# basic.net
KiCad netlist of a schematic drawn in EAGLE
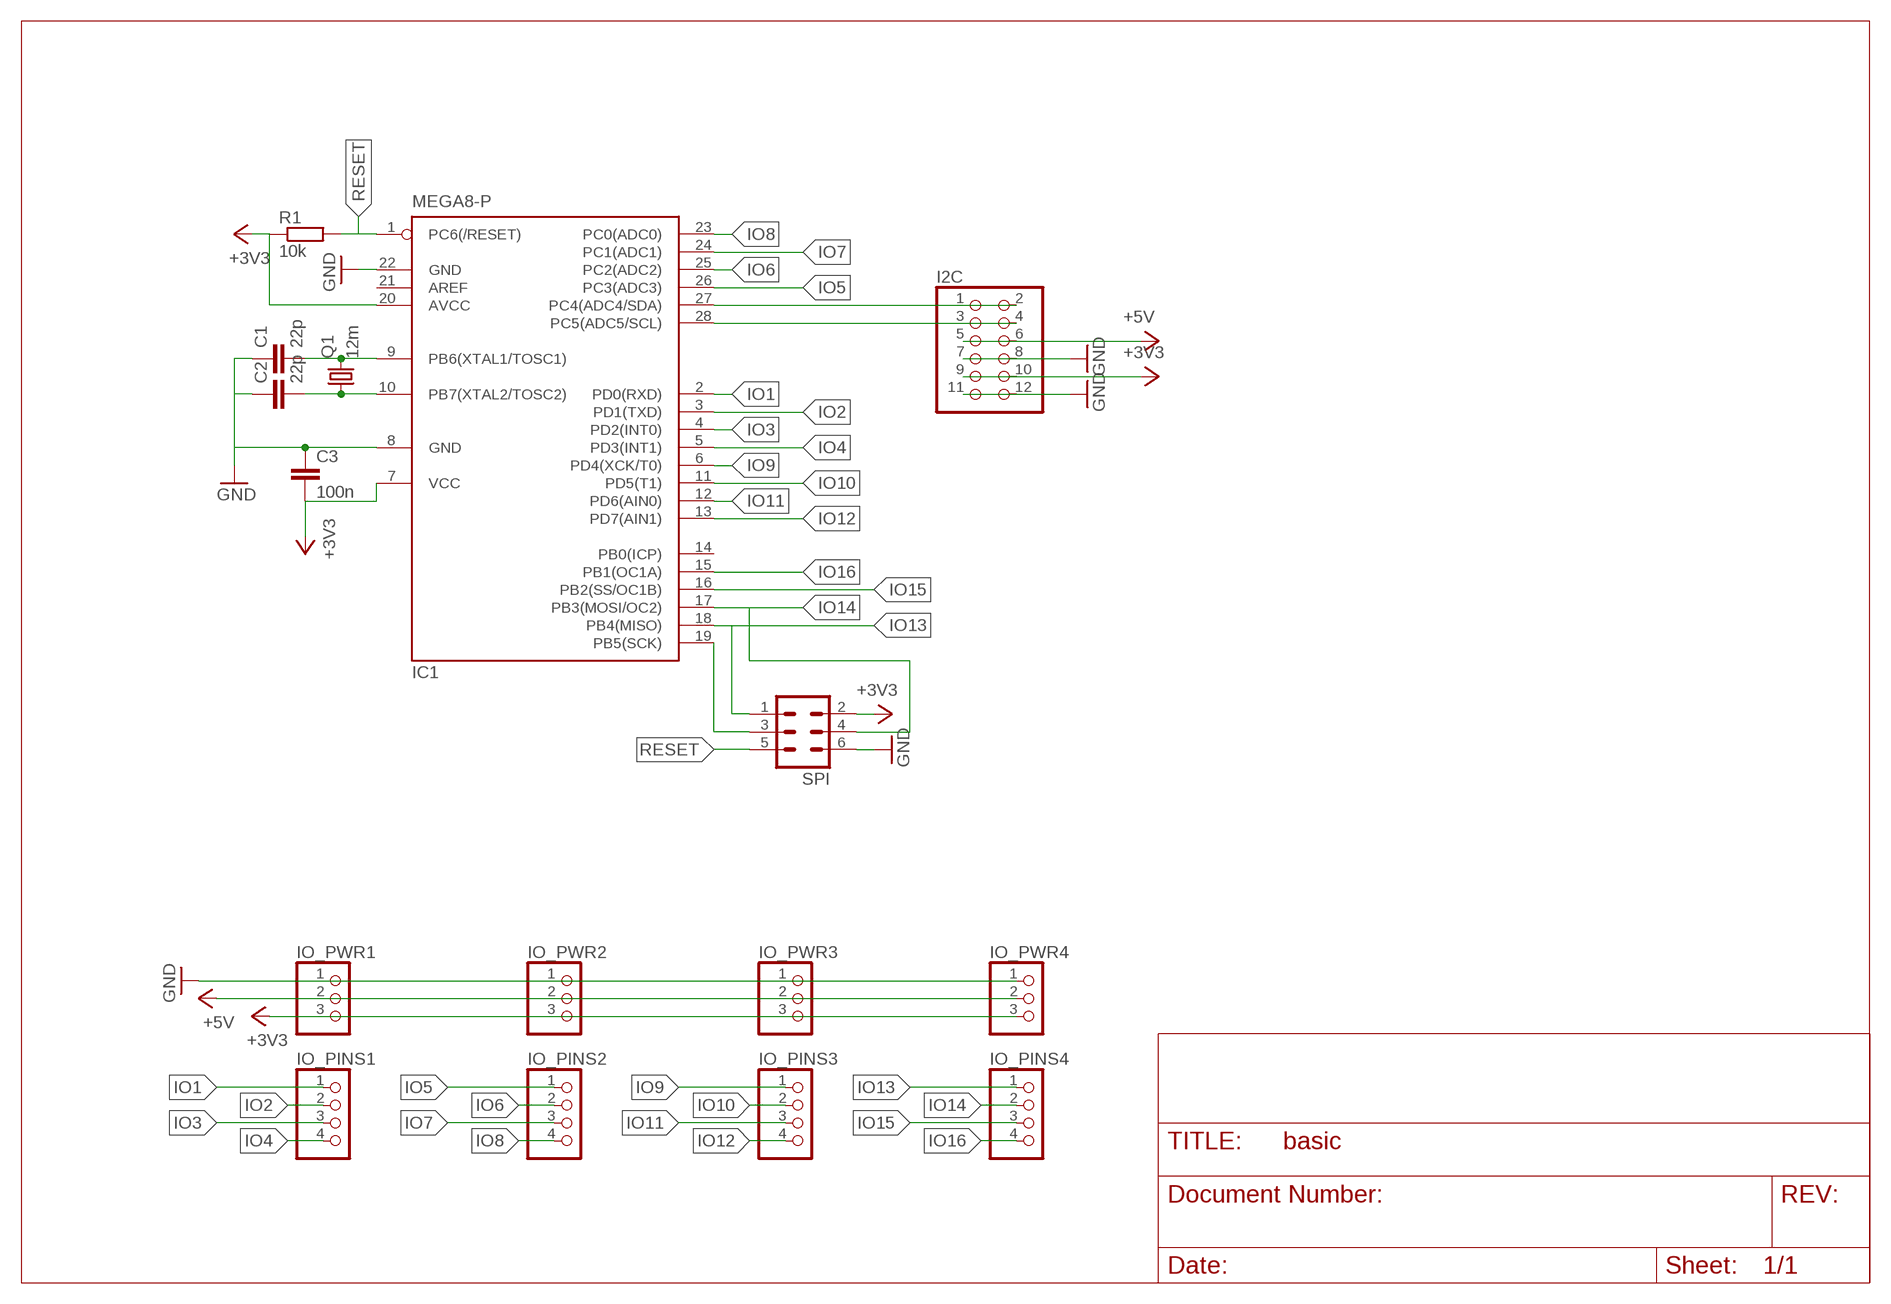
[diagram p0: schematic, sheet 1]

(export (version "E")
  (design (tool "Eeschema 10.0.6"))
  (components
    (comp (ref "C1")
      (value "22p")
      (footprint "eagle-import:C025-025X050")
      (libsource (lib "eagle-import") (part "C-EU025-025X050"))
    )
    (comp (ref "C2")
      (value "22p")
      (footprint "eagle-import:C025-025X050")
      (libsource (lib "eagle-import") (part "C-EU025-025X050"))
    )
    (comp (ref "C3")
      (value "100n")
      (footprint "eagle-import:C025-025X050")
      (libsource (lib "eagle-import") (part "C-EU025-025X050"))
    )
    (comp (ref "I2C")
      (value "PINHD-2X6")
      (footprint "eagle-import:2X06")
      (libsource (lib "eagle-import") (part "PINHD-2X6"))
    )
    (comp (ref "IC1")
      (value "MEGA8-P")
      (footprint "eagle-import:DIL28-3")
      (libsource (lib "eagle-import") (part "MEGA8-P"))
    )
    (comp (ref "IO_PINS1")
      (value "PINHD-1X4")
      (footprint "eagle-import:1X04")
      (libsource (lib "eagle-import") (part "PINHD-1X4"))
    )
    (comp (ref "IO_PINS2")
      (value "PINHD-1X4")
      (footprint "eagle-import:1X04")
      (libsource (lib "eagle-import") (part "PINHD-1X4"))
    )
    (comp (ref "IO_PINS3")
      (value "PINHD-1X4")
      (footprint "eagle-import:1X04")
      (libsource (lib "eagle-import") (part "PINHD-1X4"))
    )
    (comp (ref "IO_PINS4")
      (value "PINHD-1X4")
      (footprint "eagle-import:1X04")
      (libsource (lib "eagle-import") (part "PINHD-1X4"))
    )
    (comp (ref "IO_PWR1")
      (value "PINHD-1X3")
      (footprint "eagle-import:1X03")
      (libsource (lib "eagle-import") (part "PINHD-1X3"))
    )
    (comp (ref "IO_PWR2")
      (value "PINHD-1X3")
      (footprint "eagle-import:1X03")
      (libsource (lib "eagle-import") (part "PINHD-1X3"))
    )
    (comp (ref "IO_PWR3")
      (value "PINHD-1X3")
      (footprint "eagle-import:1X03")
      (libsource (lib "eagle-import") (part "PINHD-1X3"))
    )
    (comp (ref "IO_PWR4")
      (value "PINHD-1X3")
      (footprint "eagle-import:1X03")
      (libsource (lib "eagle-import") (part "PINHD-1X3"))
    )
    (comp (ref "Q1")
      (value "12m")
      (footprint "eagle-import:HC49_S")
      (libsource (lib "eagle-import") (part "CRYSTALHC49S"))
    )
    (comp (ref "R1")
      (value "10k")
      (footprint "eagle-import:0207_10")
      (libsource (lib "eagle-import") (part "R-EU_0207/10"))
    )
    (comp (ref "SPI")
      (value "ML6")
      (footprint "eagle-import:ML6")
      (libsource (lib "eagle-import") (part "ML6"))
    )
  )
  (nets
    (net (code "1") (name "+3V3") (class "Default")
      (node (ref "C3") (pin "2") (pinfunction "2_2") (pintype "passive"))
      (node (ref "I2C") (pin "10") (pinfunction "10_10") (pintype "passive"))
      (node (ref "I2C") (pin "9") (pinfunction "9_9") (pintype "passive"))
      (node (ref "IC1") (pin "20") (pinfunction "AVCC_20") (pintype "power_in"))
      (node (ref "IC1") (pin "7") (pinfunction "VCC_7") (pintype "power_in"))
      (node (ref "IO_PWR1") (pin "3") (pinfunction "3_3") (pintype "passive"))
      (node (ref "IO_PWR2") (pin "3") (pinfunction "3_3") (pintype "passive"))
      (node (ref "IO_PWR3") (pin "3") (pinfunction "3_3") (pintype "passive"))
      (node (ref "IO_PWR4") (pin "3") (pinfunction "3_3") (pintype "passive"))
      (node (ref "R1") (pin "1") (pinfunction "1_1") (pintype "passive"))
      (node (ref "SPI") (pin "2") (pinfunction "2_2") (pintype "passive"))
    )
    (net (code "2") (name "+5V") (class "Default")
      (node (ref "I2C") (pin "5") (pinfunction "5_5") (pintype "passive"))
      (node (ref "I2C") (pin "6") (pinfunction "6_6") (pintype "passive"))
      (node (ref "IO_PWR1") (pin "2") (pinfunction "2_2") (pintype "passive"))
      (node (ref "IO_PWR2") (pin "2") (pinfunction "2_2") (pintype "passive"))
      (node (ref "IO_PWR3") (pin "2") (pinfunction "2_2") (pintype "passive"))
      (node (ref "IO_PWR4") (pin "2") (pinfunction "2_2") (pintype "passive"))
    )
    (net (code "3") (name "GND") (class "Default")
      (node (ref "C1") (pin "1") (pinfunction "1_1") (pintype "passive"))
      (node (ref "C2") (pin "1") (pinfunction "1_1") (pintype "passive"))
      (node (ref "C3") (pin "1") (pinfunction "1_1") (pintype "passive"))
      (node (ref "I2C") (pin "11") (pinfunction "11_11") (pintype "passive"))
      (node (ref "I2C") (pin "12") (pinfunction "12_12") (pintype "passive"))
      (node (ref "I2C") (pin "7") (pinfunction "7_7") (pintype "passive"))
      (node (ref "I2C") (pin "8") (pinfunction "8_8") (pintype "passive"))
      (node (ref "IC1") (pin "22") (pinfunction "GND_22") (pintype "power_in"))
      (node (ref "IC1") (pin "8") (pinfunction "GND_8") (pintype "power_in"))
      (node (ref "IO_PWR1") (pin "1") (pinfunction "1_1") (pintype "passive"))
      (node (ref "IO_PWR2") (pin "1") (pinfunction "1_1") (pintype "passive"))
      (node (ref "IO_PWR3") (pin "1") (pinfunction "1_1") (pintype "passive"))
      (node (ref "IO_PWR4") (pin "1") (pinfunction "1_1") (pintype "passive"))
      (node (ref "SPI") (pin "6") (pinfunction "6_6") (pintype "passive"))
    )
    (net (code "4") (name "IO1") (class "Default")
      (node (ref "IC1") (pin "2") (pinfunction "PD0(RXD)_2") (pintype "bidirectional"))
      (node (ref "IO_PINS1") (pin "1") (pinfunction "1_1") (pintype "passive"))
    )
    (net (code "5") (name "IO2") (class "Default")
      (node (ref "IC1") (pin "3") (pinfunction "PD1(TXD)_3") (pintype "bidirectional"))
      (node (ref "IO_PINS1") (pin "2") (pinfunction "2_2") (pintype "passive"))
    )
    (net (code "6") (name "IO3") (class "Default")
      (node (ref "IC1") (pin "4") (pinfunction "PD2(INT0)_4") (pintype "bidirectional"))
      (node (ref "IO_PINS1") (pin "3") (pinfunction "3_3") (pintype "passive"))
    )
    (net (code "7") (name "IO4") (class "Default")
      (node (ref "IC1") (pin "5") (pinfunction "PD3(INT1)_5") (pintype "bidirectional"))
      (node (ref "IO_PINS1") (pin "4") (pinfunction "4_4") (pintype "passive"))
    )
    (net (code "8") (name "IO5") (class "Default")
      (node (ref "IC1") (pin "26") (pinfunction "PC3(ADC3)_26") (pintype "bidirectional"))
      (node (ref "IO_PINS2") (pin "1") (pinfunction "1_1") (pintype "passive"))
    )
    (net (code "9") (name "IO6") (class "Default")
      (node (ref "IC1") (pin "25") (pinfunction "PC2(ADC2)_25") (pintype "bidirectional"))
      (node (ref "IO_PINS2") (pin "2") (pinfunction "2_2") (pintype "passive"))
    )
    (net (code "10") (name "IO7") (class "Default")
      (node (ref "IC1") (pin "24") (pinfunction "PC1(ADC1)_24") (pintype "bidirectional"))
      (node (ref "IO_PINS2") (pin "3") (pinfunction "3_3") (pintype "passive"))
    )
    (net (code "11") (name "IO8") (class "Default")
      (node (ref "IC1") (pin "23") (pinfunction "PC0(ADC0)_23") (pintype "bidirectional"))
      (node (ref "IO_PINS2") (pin "4") (pinfunction "4_4") (pintype "passive"))
    )
    (net (code "12") (name "IO9") (class "Default")
      (node (ref "IC1") (pin "6") (pinfunction "PD4(XCK/T0)_6") (pintype "bidirectional"))
      (node (ref "IO_PINS3") (pin "1") (pinfunction "1_1") (pintype "passive"))
    )
    (net (code "13") (name "IO10") (class "Default")
      (node (ref "IC1") (pin "11") (pinfunction "PD5(T1)_11") (pintype "bidirectional"))
      (node (ref "IO_PINS3") (pin "2") (pinfunction "2_2") (pintype "passive"))
    )
    (net (code "14") (name "IO11") (class "Default")
      (node (ref "IC1") (pin "12") (pinfunction "PD6(AIN0)_12") (pintype "bidirectional"))
      (node (ref "IO_PINS3") (pin "3") (pinfunction "3_3") (pintype "passive"))
    )
    (net (code "15") (name "IO12") (class "Default")
      (node (ref "IC1") (pin "13") (pinfunction "PD7(AIN1)_13") (pintype "bidirectional"))
      (node (ref "IO_PINS3") (pin "4") (pinfunction "4_4") (pintype "passive"))
    )
    (net (code "16") (name "IO13") (class "Default")
      (node (ref "IC1") (pin "18") (pinfunction "PB4(MISO)_18") (pintype "bidirectional"))
      (node (ref "IO_PINS4") (pin "1") (pinfunction "1_1") (pintype "passive"))
      (node (ref "SPI") (pin "1") (pinfunction "1_1") (pintype "passive"))
    )
    (net (code "17") (name "IO14") (class "Default")
      (node (ref "IC1") (pin "17") (pinfunction "PB3(MOSI/OC2)_17") (pintype "bidirectional"))
      (node (ref "IO_PINS4") (pin "2") (pinfunction "2_2") (pintype "passive"))
      (node (ref "SPI") (pin "4") (pinfunction "4_4") (pintype "passive"))
    )
    (net (code "18") (name "IO15") (class "Default")
      (node (ref "IC1") (pin "16") (pinfunction "PB2(SS/OC1B)_16") (pintype "bidirectional"))
      (node (ref "IO_PINS4") (pin "3") (pinfunction "3_3") (pintype "passive"))
    )
    (net (code "19") (name "IO16") (class "Default")
      (node (ref "IC1") (pin "15") (pinfunction "PB1(OC1A)_15") (pintype "bidirectional"))
      (node (ref "IO_PINS4") (pin "4") (pinfunction "4_4") (pintype "passive"))
    )
    (net (code "20") (name "Net-(IC1-PB5(SCK))") (class "Default")
      (node (ref "IC1") (pin "19") (pinfunction "PB5(SCK)_19") (pintype "bidirectional"))
      (node (ref "SPI") (pin "3") (pinfunction "3_3") (pintype "passive"))
    )
    (net (code "21") (name "Net-(IC1-PB6(XTAL1{slash}TOSC1))") (class "Default")
      (node (ref "C1") (pin "2") (pinfunction "2_2") (pintype "passive"))
      (node (ref "IC1") (pin "9") (pinfunction "PB6(XTAL1/TOSC1)_9") (pintype "bidirectional"))
      (node (ref "Q1") (pin "2") (pinfunction "2_2") (pintype "passive"))
    )
    (net (code "22") (name "Net-(IC1-PB7(XTAL2{slash}TOSC2))") (class "Default")
      (node (ref "C2") (pin "2") (pinfunction "2_2") (pintype "passive"))
      (node (ref "IC1") (pin "10") (pinfunction "PB7(XTAL2/TOSC2)_10") (pintype "bidirectional"))
      (node (ref "Q1") (pin "1") (pinfunction "1_1") (pintype "passive"))
    )
    (net (code "23") (name "Net-(IC1-PC4(ADC4{slash}SDA))") (class "Default")
      (node (ref "I2C") (pin "1") (pinfunction "1_1") (pintype "passive"))
      (node (ref "I2C") (pin "2") (pinfunction "2_2") (pintype "passive"))
      (node (ref "IC1") (pin "27") (pinfunction "PC4(ADC4/SDA)_27") (pintype "bidirectional"))
    )
    (net (code "24") (name "Net-(IC1-PC5(ADC5{slash}SCL))") (class "Default")
      (node (ref "I2C") (pin "3") (pinfunction "3_3") (pintype "passive"))
      (node (ref "I2C") (pin "4") (pinfunction "4_4") (pintype "passive"))
      (node (ref "IC1") (pin "28") (pinfunction "PC5(ADC5/SCL)_28") (pintype "bidirectional"))
    )
    (net (code "25") (name "RESET") (class "Default")
      (node (ref "IC1") (pin "1") (pinfunction "PC6(/RESET)_1") (pintype "bidirectional"))
      (node (ref "R1") (pin "2") (pinfunction "2_2") (pintype "passive"))
      (node (ref "SPI") (pin "5") (pinfunction "5_5") (pintype "passive"))
    )
    (net (code "26") (name "unconnected-(IC1-AREF-Pad21)") (class "Default")
      (node (ref "IC1") (pin "21") (pinfunction "AREF_21") (pintype "passive"))
    )
    (net (code "27") (name "unconnected-(IC1-PB0(ICP)-Pad14)") (class "Default")
      (node (ref "IC1") (pin "14") (pinfunction "PB0(ICP)_14") (pintype "bidirectional"))
    )
  )
)
